# PM_Drive_UI.net
KiCad netlist of a schematic drawn in Altium Designer
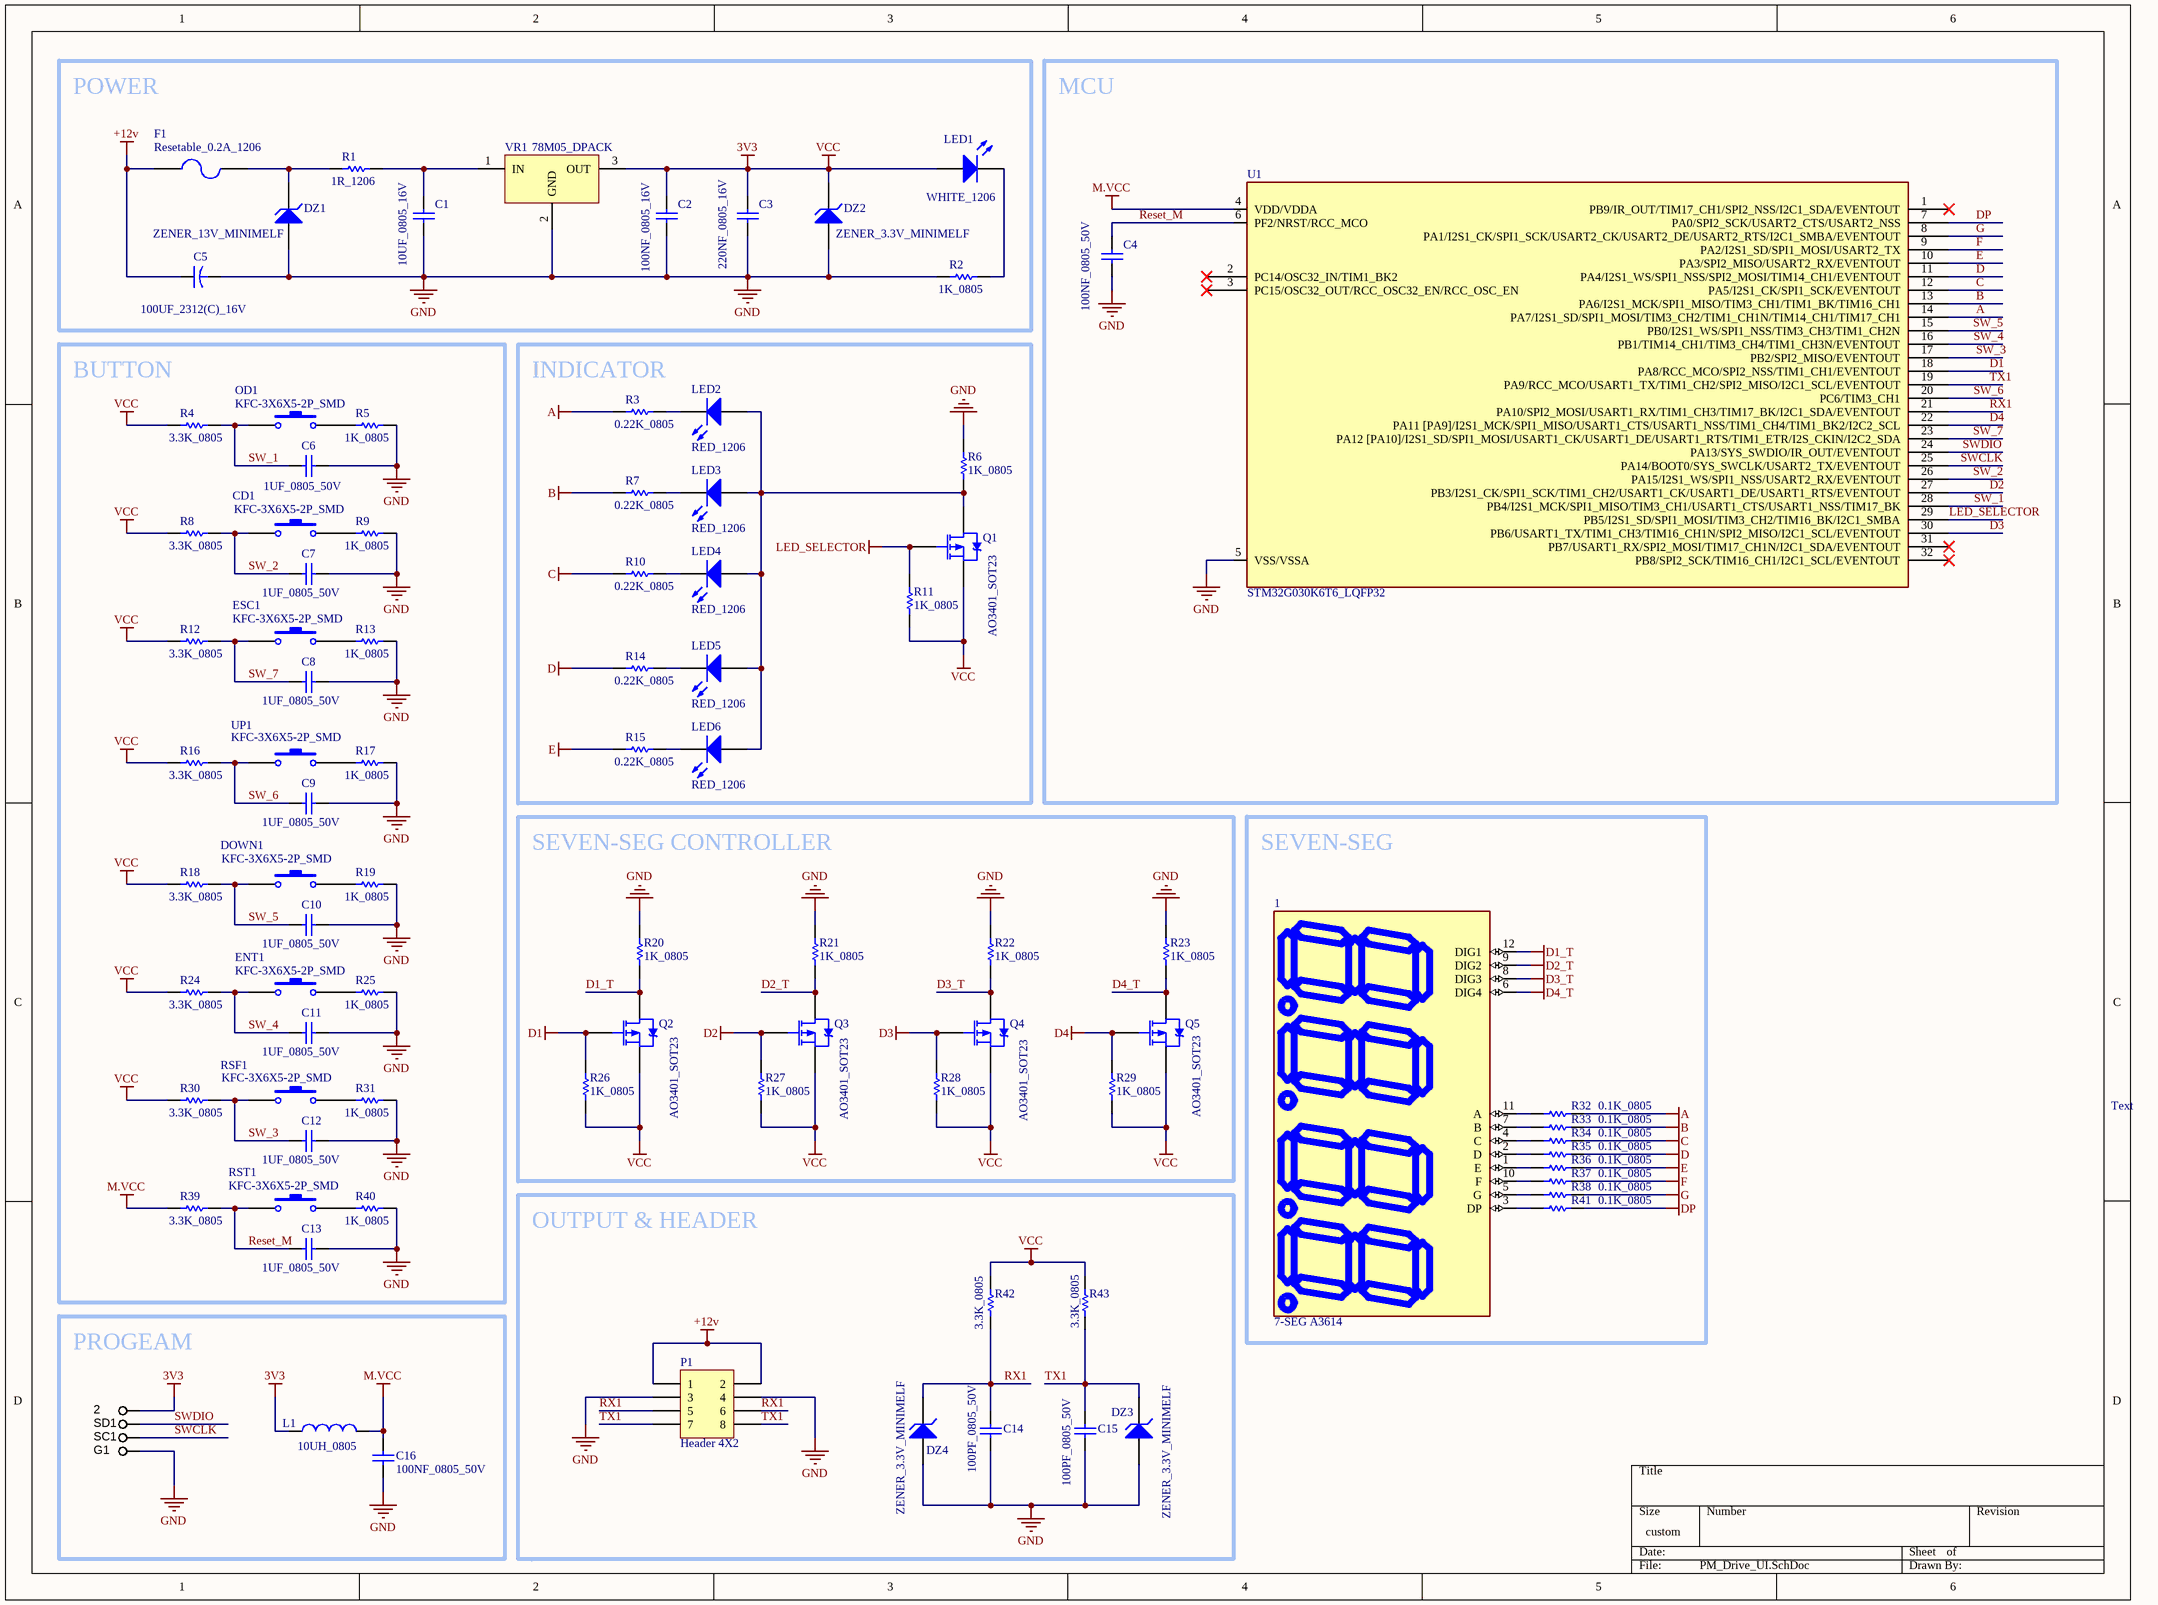
[diagram p0: PM_Drive_UI.SchDoc]

(export (version "E")
  (design (tool "Eeschema 10.0.6"))
  (components
    (comp (ref "1")
      (value "7-SEG A3614")
      (footprint "7Seg_4Digit")
      (libsource (lib "Amirreza") (part "7SEG-4DIGT-12mm"))
    )
    (comp (ref "2")
      (value "~")
      (footprint "TPSMD_D1")
      (description "TEST POINT")
      (fields (field (name "MANF") "MANF") (field (name "MANF_P#") "MANF_P#"))
      (libsource (lib "GTC Schematic") (part "TESTPOINT_SMD"))
    )
    (comp (ref "C1")
      (value "10UF_0805_16V")
      (footprint "Cap_0805_Nominal")
      (libsource (lib "Saeed_New_Lib") (part "Cap"))
    )
    (comp (ref "C2")
      (value "100NF_0805_16V")
      (footprint "Cap_0805_Nominal")
      (libsource (lib "Saeed_New_Lib") (part "Cap"))
    )
    (comp (ref "C3")
      (value "220NF_0805_16V")
      (footprint "Cap_0805_Nominal")
      (libsource (lib "Saeed_New_Lib") (part "Cap"))
    )
    (comp (ref "C4")
      (value "100NF_0805_50V")
      (footprint "Cap_0805_Nominal")
      (libsource (lib "Saeed_New_Lib") (part "Cap"))
    )
    (comp (ref "C5")
      (value "100UF_2312(C)_16V")
      (footprint "Cap_Tantal(6032)_C")
      (libsource (lib "GTC Shem") (part "Cap_Electrical"))
    )
    (comp (ref "C6")
      (value "1UF_0805_50V")
      (footprint "Cap_0805_Nominal")
      (libsource (lib "Saeed_New_Lib") (part "Cap"))
    )
    (comp (ref "C7")
      (value "1UF_0805_50V")
      (footprint "Cap_0805_Nominal")
      (libsource (lib "Saeed_New_Lib") (part "Cap"))
    )
    (comp (ref "C8")
      (value "1UF_0805_50V")
      (footprint "Cap_0805_Nominal")
      (libsource (lib "Saeed_New_Lib") (part "Cap"))
    )
    (comp (ref "C9")
      (value "1UF_0805_50V")
      (footprint "Cap_0805_Nominal")
      (libsource (lib "Saeed_New_Lib") (part "Cap"))
    )
    (comp (ref "C10")
      (value "1UF_0805_50V")
      (footprint "Cap_0805_Nominal")
      (libsource (lib "Saeed_New_Lib") (part "Cap"))
    )
    (comp (ref "C11")
      (value "1UF_0805_50V")
      (footprint "Cap_0805_Nominal")
      (libsource (lib "Saeed_New_Lib") (part "Cap"))
    )
    (comp (ref "C12")
      (value "1UF_0805_50V")
      (footprint "Cap_0805_Nominal")
      (libsource (lib "Saeed_New_Lib") (part "Cap"))
    )
    (comp (ref "C13")
      (value "1UF_0805_50V")
      (footprint "Cap_0805_Nominal")
      (libsource (lib "Saeed_New_Lib") (part "Cap"))
    )
    (comp (ref "C14")
      (value "100PF_0805_50V")
      (footprint "Cap_0805_Nominal")
      (libsource (lib "Saeed_New_Lib") (part "Cap"))
    )
    (comp (ref "C15")
      (value "100PF_0805_50V")
      (footprint "Cap_0805_Nominal")
      (libsource (lib "Saeed_New_Lib") (part "Cap"))
    )
    (comp (ref "C16")
      (value "100NF_0805_50V")
      (footprint "Cap_0805_Nominal")
      (libsource (lib "Saeed_New_Lib") (part "Cap"))
    )
    (comp (ref "CD1")
      (value "KFC-3X6X5-2P_SMD")
      (footprint "SWPBS_SPST_6X3X5")
      (description "Switch")
      (fields (field (name "PUBLISHER") "Altium Limited"))
      (libsource (lib "Miscellaneous Devices") (part "SW-PB"))
    )
    (comp (ref "DOWN1")
      (value "KFC-3X6X5-2P_SMD")
      (footprint "SWPBS_SPST_6X3X5")
      (description "Switch")
      (fields (field (name "PUBLISHER") "Altium Limited"))
      (libsource (lib "Miscellaneous Devices") (part "SW-PB"))
    )
    (comp (ref "DZ1")
      (value "ZENER_13V_MINIMELF")
      (footprint "Diode_ZENER_MINIMELF")
      (libsource (lib "Amirreza") (part "Diode_Zener"))
    )
    (comp (ref "DZ2")
      (value "ZENER_3.3V_MINIMELF")
      (footprint "Diode_ZENER_MINIMELF")
      (libsource (lib "Amirreza") (part "Diode_Zener"))
    )
    (comp (ref "DZ3")
      (value "ZENER_3.3V_MINIMELF")
      (footprint "Diode_ZENER_MINIMELF")
      (libsource (lib "Amirreza") (part "Diode_Zener"))
    )
    (comp (ref "DZ4")
      (value "ZENER_3.3V_MINIMELF")
      (footprint "Diode_ZENER_MINIMELF")
      (libsource (lib "Amirreza") (part "Diode_Zener"))
    )
    (comp (ref "ENT1")
      (value "KFC-3X6X5-2P_SMD")
      (footprint "SWPBS_SPST_6X3X5")
      (description "Switch")
      (fields (field (name "PUBLISHER") "Altium Limited"))
      (libsource (lib "Miscellaneous Devices") (part "SW-PB"))
    )
    (comp (ref "ESC1")
      (value "KFC-3X6X5-2P_SMD")
      (footprint "SWPBS_SPST_6X3X5")
      (description "Switch")
      (fields (field (name "PUBLISHER") "Altium Limited"))
      (libsource (lib "Miscellaneous Devices") (part "SW-PB"))
    )
    (comp (ref "F1")
      (value "Resetable_0.2A_1206")
      (footprint "FUSE_1206")
      (libsource (lib "Amirreza") (part "FUSE"))
    )
    (comp (ref "G1")
      (value "~")
      (footprint "TPSMD_D1")
      (description "TEST POINT")
      (fields (field (name "MANF") "MANF") (field (name "MANF_P#") "MANF_P#"))
      (libsource (lib "GTC Schematic") (part "TESTPOINT_SMD"))
    )
    (comp (ref "L1")
      (value "10UH_0805")
      (footprint "INDUCTOR_0805_Nominal")
      (libsource (lib "Saeed_New_Lib") (part "Inductor"))
    )
    (comp (ref "LED1")
      (value "WHITE_1206")
      (footprint "LED_1206_NOMINAL")
      (libsource (lib "GTC Shem") (part "LED"))
    )
    (comp (ref "LED2")
      (value "RED_1206")
      (footprint "LED_1206_NOMINAL")
      (libsource (lib "GTC Shem") (part "LED"))
    )
    (comp (ref "LED3")
      (value "RED_1206")
      (footprint "LED_1206_NOMINAL")
      (libsource (lib "GTC Shem") (part "LED"))
    )
    (comp (ref "LED4")
      (value "RED_1206")
      (footprint "LED_1206_NOMINAL")
      (libsource (lib "GTC Shem") (part "LED"))
    )
    (comp (ref "LED5")
      (value "RED_1206")
      (footprint "LED_1206_NOMINAL")
      (libsource (lib "GTC Shem") (part "LED"))
    )
    (comp (ref "LED6")
      (value "RED_1206")
      (footprint "LED_1206_NOMINAL")
      (libsource (lib "GTC Shem") (part "LED"))
    )
    (comp (ref "OD1")
      (value "KFC-3X6X5-2P_SMD")
      (footprint "SWPBS_SPST_6X3X5")
      (description "Switch")
      (fields (field (name "PUBLISHER") "Altium Limited"))
      (libsource (lib "Miscellaneous Devices") (part "SW-PB"))
    )
    (comp (ref "P1")
      (value "Header 4X2")
      (footprint "HDR_M_2X4_2.54MM")
      (description "Header, 6-Pin, Dual row")
      (fields (field (name "PUBLISHER") "Altium Limited"))
      (libsource (lib "Amirreza") (part "Header 4X2"))
    )
    (comp (ref "Q1")
      (value "AO3401_SOT23")
      (footprint "SOT23_MOSFET")
      (description "P-Channel MOSFET")
      (fields (field (name "PUBLISHER") "Altium Limited"))
      (libsource (lib "Amirreza") (part "MOSFET-P"))
    )
    (comp (ref "Q2")
      (value "AO3401_SOT23")
      (footprint "SOT23_MOSFET")
      (description "P-Channel MOSFET")
      (fields (field (name "PUBLISHER") "Altium Limited"))
      (libsource (lib "Amirreza") (part "MOSFET-P"))
    )
    (comp (ref "Q3")
      (value "AO3401_SOT23")
      (footprint "SOT23_MOSFET")
      (description "P-Channel MOSFET")
      (fields (field (name "PUBLISHER") "Altium Limited"))
      (libsource (lib "Amirreza") (part "MOSFET-P"))
    )
    (comp (ref "Q4")
      (value "AO3401_SOT23")
      (footprint "SOT23_MOSFET")
      (description "P-Channel MOSFET")
      (fields (field (name "PUBLISHER") "Altium Limited"))
      (libsource (lib "Amirreza") (part "MOSFET-P"))
    )
    (comp (ref "Q5")
      (value "AO3401_SOT23")
      (footprint "SOT23_MOSFET")
      (description "P-Channel MOSFET")
      (fields (field (name "PUBLISHER") "Altium Limited"))
      (libsource (lib "Amirreza") (part "MOSFET-P"))
    )
    (comp (ref "R1")
      (value "1R_1206")
      (footprint "Res_1206_BIG SIZE")
      (libsource (lib "Amir_Library") (part "RES"))
    )
    (comp (ref "R2")
      (value "1K_0805")
      (footprint "Res_0805_Nominal")
      (libsource (lib "Amir_Library") (part "RES"))
    )
    (comp (ref "R3")
      (value "0.22K_0805")
      (footprint "Res_0805_Nominal")
      (libsource (lib "Amir_Library") (part "RES"))
    )
    (comp (ref "R4")
      (value "3.3K_0805")
      (footprint "Res_0805_Nominal")
      (libsource (lib "Amir_Library") (part "RES"))
    )
    (comp (ref "R5")
      (value "1K_0805")
      (footprint "Res_0805_Nominal")
      (libsource (lib "Amir_Library") (part "RES"))
    )
    (comp (ref "R6")
      (value "1K_0805")
      (footprint "Res_0805_Nominal")
      (libsource (lib "Amir_Library") (part "RES"))
    )
    (comp (ref "R7")
      (value "0.22K_0805")
      (footprint "Res_0805_Nominal")
      (libsource (lib "Amir_Library") (part "RES"))
    )
    (comp (ref "R8")
      (value "3.3K_0805")
      (footprint "Res_0805_Nominal")
      (libsource (lib "Amir_Library") (part "RES"))
    )
    (comp (ref "R9")
      (value "1K_0805")
      (footprint "Res_0805_Nominal")
      (libsource (lib "Amir_Library") (part "RES"))
    )
    (comp (ref "R10")
      (value "0.22K_0805")
      (footprint "Res_0805_Nominal")
      (libsource (lib "Amir_Library") (part "RES"))
    )
    (comp (ref "R11")
      (value "1K_0805")
      (footprint "Res_0805_Nominal")
      (libsource (lib "Amir_Library") (part "RES"))
    )
    (comp (ref "R12")
      (value "3.3K_0805")
      (footprint "Res_0805_Nominal")
      (libsource (lib "Amir_Library") (part "RES"))
    )
    (comp (ref "R13")
      (value "1K_0805")
      (footprint "Res_0805_Nominal")
      (libsource (lib "Amir_Library") (part "RES"))
    )
    (comp (ref "R14")
      (value "0.22K_0805")
      (footprint "Res_0805_Nominal")
      (libsource (lib "Amir_Library") (part "RES"))
    )
    (comp (ref "R15")
      (value "0.22K_0805")
      (footprint "Res_0805_Nominal")
      (libsource (lib "Amir_Library") (part "RES"))
    )
    (comp (ref "R16")
      (value "3.3K_0805")
      (footprint "Res_0805_Nominal")
      (libsource (lib "Amir_Library") (part "RES"))
    )
    (comp (ref "R17")
      (value "1K_0805")
      (footprint "Res_0805_Nominal")
      (libsource (lib "Amir_Library") (part "RES"))
    )
    (comp (ref "R18")
      (value "3.3K_0805")
      (footprint "Res_0805_Nominal")
      (libsource (lib "Amir_Library") (part "RES"))
    )
    (comp (ref "R19")
      (value "1K_0805")
      (footprint "Res_0805_Nominal")
      (libsource (lib "Amir_Library") (part "RES"))
    )
    (comp (ref "R20")
      (value "1K_0805")
      (footprint "Res_0805_Nominal")
      (libsource (lib "Amir_Library") (part "RES"))
    )
    (comp (ref "R21")
      (value "1K_0805")
      (footprint "Res_0805_Nominal")
      (libsource (lib "Amir_Library") (part "RES"))
    )
    (comp (ref "R22")
      (value "1K_0805")
      (footprint "Res_0805_Nominal")
      (libsource (lib "Amir_Library") (part "RES"))
    )
    (comp (ref "R23")
      (value "1K_0805")
      (footprint "Res_0805_Nominal")
      (libsource (lib "Amir_Library") (part "RES"))
    )
    (comp (ref "R24")
      (value "3.3K_0805")
      (footprint "Res_0805_Nominal")
      (libsource (lib "Amir_Library") (part "RES"))
    )
    (comp (ref "R25")
      (value "1K_0805")
      (footprint "Res_0805_Nominal")
      (libsource (lib "Amir_Library") (part "RES"))
    )
    (comp (ref "R26")
      (value "1K_0805")
      (footprint "Res_0805_Nominal")
      (libsource (lib "Amir_Library") (part "RES"))
    )
    (comp (ref "R27")
      (value "1K_0805")
      (footprint "Res_0805_Nominal")
      (libsource (lib "Amir_Library") (part "RES"))
    )
    (comp (ref "R28")
      (value "1K_0805")
      (footprint "Res_0805_Nominal")
      (libsource (lib "Amir_Library") (part "RES"))
    )
    (comp (ref "R29")
      (value "1K_0805")
      (footprint "Res_0805_Nominal")
      (libsource (lib "Amir_Library") (part "RES"))
    )
    (comp (ref "R30")
      (value "3.3K_0805")
      (footprint "Res_0805_Nominal")
      (libsource (lib "Amir_Library") (part "RES"))
    )
    (comp (ref "R31")
      (value "1K_0805")
      (footprint "Res_0805_Nominal")
      (libsource (lib "Amir_Library") (part "RES"))
    )
    (comp (ref "R32")
      (value "0.1K_0805")
      (footprint "Res_0805_Nominal")
      (libsource (lib "Amir_Library") (part "RES"))
    )
    (comp (ref "R33")
      (value "0.1K_0805")
      (footprint "Res_0805_Nominal")
      (libsource (lib "Amir_Library") (part "RES"))
    )
    (comp (ref "R34")
      (value "0.1K_0805")
      (footprint "Res_0805_Nominal")
      (libsource (lib "Amir_Library") (part "RES"))
    )
    (comp (ref "R35")
      (value "0.1K_0805")
      (footprint "Res_0805_Nominal")
      (libsource (lib "Amir_Library") (part "RES"))
    )
    (comp (ref "R36")
      (value "0.1K_0805")
      (footprint "Res_0805_Nominal")
      (libsource (lib "Amir_Library") (part "RES"))
    )
    (comp (ref "R37")
      (value "0.1K_0805")
      (footprint "Res_0805_Nominal")
      (libsource (lib "Amir_Library") (part "RES"))
    )
    (comp (ref "R38")
      (value "0.1K_0805")
      (footprint "Res_0805_Nominal")
      (libsource (lib "Amir_Library") (part "RES"))
    )
    (comp (ref "R39")
      (value "3.3K_0805")
      (footprint "Res_0805_Nominal")
      (libsource (lib "Amir_Library") (part "RES"))
    )
    (comp (ref "R40")
      (value "1K_0805")
      (footprint "Res_0805_Nominal")
      (libsource (lib "Amir_Library") (part "RES"))
    )
    (comp (ref "R41")
      (value "0.1K_0805")
      (footprint "Res_0805_Nominal")
      (libsource (lib "Amir_Library") (part "RES"))
    )
    (comp (ref "R42")
      (value "3.3K_0805")
      (footprint "Res_0805_Nominal")
      (libsource (lib "Amir_Library") (part "RES"))
    )
    (comp (ref "R43")
      (value "3.3K_0805")
      (footprint "Res_0805_Nominal")
      (libsource (lib "Amir_Library") (part "RES"))
    )
    (comp (ref "RSF1")
      (value "KFC-3X6X5-2P_SMD")
      (footprint "SWPBS_SPST_6X3X5")
      (description "Switch")
      (fields (field (name "PUBLISHER") "Altium Limited"))
      (libsource (lib "Miscellaneous Devices") (part "SW-PB"))
    )
    (comp (ref "RST1")
      (value "KFC-3X6X5-2P_SMD")
      (footprint "SWPBS_SPST_6X3X5")
      (description "Switch")
      (fields (field (name "PUBLISHER") "Altium Limited"))
      (libsource (lib "Miscellaneous Devices") (part "SW-PB"))
    )
    (comp (ref "SC1")
      (value "~")
      (footprint "TPSMD_D1")
      (description "TEST POINT")
      (fields (field (name "MANF") "MANF") (field (name "MANF_P#") "MANF_P#"))
      (libsource (lib "GTC Schematic") (part "TESTPOINT_SMD"))
    )
    (comp (ref "SD1")
      (value "~")
      (footprint "TPSMD_D1")
      (description "TEST POINT")
      (fields (field (name "MANF") "MANF") (field (name "MANF_P#") "MANF_P#"))
      (libsource (lib "GTC Schematic") (part "TESTPOINT_SMD"))
    )
    (comp (ref "U1")
      (value "STM32G030K6T6_LQFP32")
      (footprint "QFG80_32")
      (fields (field (name "MANF") "ST") (field (name "MANF_P#") "STM32G030K6T6"))
      (libsource (lib "Amirreza") (part "STM32G030K6T6"))
    )
    (comp (ref "UP1")
      (value "KFC-3X6X5-2P_SMD")
      (footprint "SWPBS_SPST_6X3X5")
      (description "Switch")
      (fields (field (name "PUBLISHER") "Altium Limited"))
      (libsource (lib "Miscellaneous Devices") (part "SW-PB"))
    )
    (comp (ref "VR1") (value "78M05_DPACK") (footprint "DPAK") (libsource (lib "Amirreza") (part "78M05")))
  )
  (nets
    (net (code "1") (name "+12v") (class "Default")
      (node (ref "C5") (pin "1") (pinfunction "1_1") (pintype "passive"))
      (node (ref "F1") (pin "1") (pinfunction "1_1") (pintype "passive"))
      (node (ref "P1") (pin "1") (pinfunction "1_1") (pintype "passive"))
      (node (ref "P1") (pin "2") (pinfunction "2_2") (pintype "passive"))
    )
    (net (code "2") (name "/RX1") (class "Default")
      (node (ref "C14") (pin "1") (pinfunction "1_1") (pintype "passive"))
      (node (ref "DZ4") (pin "2") (pinfunction "K_2") (pintype "passive"))
      (node (ref "P1") (pin "5") (pinfunction "5_5") (pintype "passive"))
      (node (ref "P1") (pin "6") (pinfunction "6_6") (pintype "passive"))
      (node (ref "R42") (pin "1") (pinfunction "1_1") (pintype "passive"))
      (node (ref "U1") (pin "21") (pinfunction "PA10/SPI2_MOSI/USART1_RX/TIM1_CH3/TIM17_BK/I2C1_SDA/EVENTOUT_21") (pintype "passive"))
    )
    (net (code "3") (name "/Reset_M") (class "Default")
      (node (ref "C13") (pin "2") (pinfunction "2_2") (pintype "passive"))
      (node (ref "C4") (pin "2") (pinfunction "2_2") (pintype "passive"))
      (node (ref "R39") (pin "2") (pinfunction "2_2") (pintype "passive"))
      (node (ref "RST1") (pin "1") (pinfunction "1_1") (pintype "passive"))
      (node (ref "U1") (pin "6") (pinfunction "PF2/NRST/RCC_MCO_6") (pintype "passive"))
    )
    (net (code "4") (name "/SWCLK") (class "Default")
      (node (ref "SC1") (pin "1") (pinfunction "1_1") (pintype "passive"))
      (node (ref "U1") (pin "25") (pinfunction "PA14/BOOT0/SYS_SWCLK/USART2_TX/EVENTOUT_25") (pintype "passive"))
    )
    (net (code "5") (name "/SWDIO") (class "Default")
      (node (ref "SD1") (pin "1") (pinfunction "1_1") (pintype "passive"))
      (node (ref "U1") (pin "24") (pinfunction "PA13/SYS_SWDIO/IR_OUT/EVENTOUT_24") (pintype "passive"))
    )
    (net (code "6") (name "/SW_1") (class "Default")
      (node (ref "C6") (pin "2") (pinfunction "2_2") (pintype "passive"))
      (node (ref "OD1") (pin "1") (pinfunction "1_1") (pintype "passive"))
      (node (ref "R4") (pin "2") (pinfunction "2_2") (pintype "passive"))
      (node (ref "U1") (pin "28") (pinfunction "PB4/I2S1_MCK/SPI1_MISO/TIM3_CH1/USART1_CTS/USART1_NSS/TIM17_BK_28") (pintype "passive"))
    )
    (net (code "7") (name "/SW_2") (class "Default")
      (node (ref "C7") (pin "2") (pinfunction "2_2") (pintype "passive"))
      (node (ref "CD1") (pin "1") (pinfunction "1_1") (pintype "passive"))
      (node (ref "R8") (pin "2") (pinfunction "2_2") (pintype "passive"))
      (node (ref "U1") (pin "26") (pinfunction "PA15/I2S1_WS/SPI1_NSS/USART2_RX/EVENTOUT_26") (pintype "passive"))
    )
    (net (code "8") (name "/SW_3") (class "Default")
      (node (ref "C12") (pin "2") (pinfunction "2_2") (pintype "passive"))
      (node (ref "R30") (pin "2") (pinfunction "2_2") (pintype "passive"))
      (node (ref "RSF1") (pin "1") (pinfunction "1_1") (pintype "passive"))
      (node (ref "U1") (pin "17") (pinfunction "PB2/SPI2_MISO/EVENTOUT_17") (pintype "passive"))
    )
    (net (code "9") (name "/SW_4") (class "Default")
      (node (ref "C11") (pin "2") (pinfunction "2_2") (pintype "passive"))
      (node (ref "ENT1") (pin "1") (pinfunction "1_1") (pintype "passive"))
      (node (ref "R24") (pin "2") (pinfunction "2_2") (pintype "passive"))
      (node (ref "U1") (pin "16") (pinfunction "PB1/TIM14_CH1/TIM3_CH4/TIM1_CH3N/EVENTOUT_16") (pintype "passive"))
    )
    (net (code "10") (name "/SW_5") (class "Default")
      (node (ref "C10") (pin "2") (pinfunction "2_2") (pintype "passive"))
      (node (ref "DOWN1") (pin "1") (pinfunction "1_1") (pintype "passive"))
      (node (ref "R18") (pin "2") (pinfunction "2_2") (pintype "passive"))
      (node (ref "U1") (pin "15") (pinfunction "PB0/I2S1_WS/SPI1_NSS/TIM3_CH3/TIM1_CH2N_15") (pintype "passive"))
    )
    (net (code "11") (name "/SW_6") (class "Default")
      (node (ref "C9") (pin "2") (pinfunction "2_2") (pintype "passive"))
      (node (ref "R16") (pin "2") (pinfunction "2_2") (pintype "passive"))
      (node (ref "U1") (pin "20") (pinfunction "PC6/TIM3_CH1_20") (pintype "passive"))
      (node (ref "UP1") (pin "1") (pinfunction "1_1") (pintype "passive"))
    )
    (net (code "12") (name "/SW_7") (class "Default")
      (node (ref "C8") (pin "2") (pinfunction "2_2") (pintype "passive"))
      (node (ref "ESC1") (pin "1") (pinfunction "1_1") (pintype "passive"))
      (node (ref "R12") (pin "2") (pinfunction "2_2") (pintype "passive"))
      (node (ref "U1") (pin "23") (pinfunction "PA12_[PA10]/I2S1_SD/SPI1_MOSI/USART1_CK/USART1_DE/USART1_RTS/TIM1_ETR/I2S_CKIN/I2C2_SDA_23") (pintype "passive"))
    )
    (net (code "13") (name "/TX1") (class "Default")
      (node (ref "C15") (pin "1") (pinfunction "1_1") (pintype "passive"))
      (node (ref "DZ3") (pin "2") (pinfunction "K_2") (pintype "passive"))
      (node (ref "P1") (pin "7") (pinfunction "7_7") (pintype "passive"))
      (node (ref "P1") (pin "8") (pinfunction "8_8") (pintype "passive"))
      (node (ref "R43") (pin "1") (pinfunction "1_1") (pintype "passive"))
      (node (ref "U1") (pin "19") (pinfunction "PA9/RCC_MCO/USART1_TX/TIM1_CH2/SPI2_MISO/I2C1_SCL/EVENTOUT_19") (pintype "passive"))
    )
    (net (code "14") (name "3V3") (class "Default")
      (node (ref "2") (pin "1") (pinfunction "1_1") (pintype "passive"))
      (node (ref "C2") (pin "2") (pinfunction "2_2") (pintype "passive"))
      (node (ref "C3") (pin "2") (pinfunction "2_2") (pintype "passive"))
      (node (ref "DZ2") (pin "2") (pinfunction "K_2") (pintype "passive"))
      (node (ref "L1") (pin "1") (pinfunction "1_1") (pintype "passive"))
      (node (ref "LED1") (pin "1") (pinfunction "A_1") (pintype "passive"))
      (node (ref "Q1") (pin "2") (pinfunction "S_2") (pintype "passive"))
      (node (ref "Q2") (pin "2") (pinfunction "S_2") (pintype "passive"))
      (node (ref "Q3") (pin "2") (pinfunction "S_2") (pintype "passive"))
      (node (ref "Q4") (pin "2") (pinfunction "S_2") (pintype "passive"))
      (node (ref "Q5") (pin "2") (pinfunction "S_2") (pintype "passive"))
      (node (ref "R11") (pin "1") (pinfunction "1_1") (pintype "passive"))
      (node (ref "R12") (pin "1") (pinfunction "1_1") (pintype "passive"))
      (node (ref "R16") (pin "1") (pinfunction "1_1") (pintype "passive"))
      (node (ref "R18") (pin "1") (pinfunction "1_1") (pintype "passive"))
      (node (ref "R24") (pin "1") (pinfunction "1_1") (pintype "passive"))
      (node (ref "R26") (pin "1") (pinfunction "1_1") (pintype "passive"))
      (node (ref "R27") (pin "1") (pinfunction "1_1") (pintype "passive"))
      (node (ref "R28") (pin "1") (pinfunction "1_1") (pintype "passive"))
      (node (ref "R29") (pin "1") (pinfunction "1_1") (pintype "passive"))
      (node (ref "R30") (pin "1") (pinfunction "1_1") (pintype "passive"))
      (node (ref "R4") (pin "1") (pinfunction "1_1") (pintype "passive"))
      (node (ref "R42") (pin "2") (pinfunction "2_2") (pintype "passive"))
      (node (ref "R43") (pin "2") (pinfunction "2_2") (pintype "passive"))
      (node (ref "R8") (pin "1") (pinfunction "1_1") (pintype "passive"))
      (node (ref "VR1") (pin "3") (pinfunction "OUT_3") (pintype "passive"))
    )
    (net (code "15") (name "A") (class "Default")
      (node (ref "R3") (pin "1") (pinfunction "1_1") (pintype "passive"))
      (node (ref "R32") (pin "2") (pinfunction "2_2") (pintype "passive"))
      (node (ref "U1") (pin "14") (pinfunction "PA7/I2S1_SD/SPI1_MOSI/TIM3_CH2/TIM1_CH1N/TIM14_CH1/TIM17_CH1_14") (pintype "passive"))
    )
    (net (code "16") (name "B") (class "Default")
      (node (ref "R33") (pin "2") (pinfunction "2_2") (pintype "passive"))
      (node (ref "R7") (pin "1") (pinfunction "1_1") (pintype "passive"))
      (node (ref "U1") (pin "13") (pinfunction "PA6/I2S1_MCK/SPI1_MISO/TIM3_CH1/TIM1_BK/TIM16_CH1_13") (pintype "passive"))
    )
    (net (code "17") (name "C") (class "Default")
      (node (ref "R10") (pin "1") (pinfunction "1_1") (pintype "passive"))
      (node (ref "R34") (pin "1") (pinfunction "1_1") (pintype "passive"))
      (node (ref "U1") (pin "12") (pinfunction "PA5/I2S1_CK/SPI1_SCK/EVENTOUT_12") (pintype "passive"))
    )
    (net (code "18") (name "D") (class "Default")
      (node (ref "R14") (pin "1") (pinfunction "1_1") (pintype "passive"))
      (node (ref "R35") (pin "1") (pinfunction "1_1") (pintype "passive"))
      (node (ref "U1") (pin "11") (pinfunction "PA4/I2S1_WS/SPI1_NSS/SPI2_MOSI/TIM14_CH1/EVENTOUT_11") (pintype "passive"))
    )
    (net (code "19") (name "D1") (class "Default")
      (node (ref "Q2") (pin "1") (pinfunction "G_1") (pintype "passive"))
      (node (ref "R26") (pin "2") (pinfunction "2_2") (pintype "passive"))
      (node (ref "U1") (pin "18") (pinfunction "PA8/RCC_MCO/SPI2_NSS/TIM1_CH1/EVENTOUT_18") (pintype "passive"))
    )
    (net (code "20") (name "D1_T") (class "Default")
      (node (ref "1") (pin "12") (pinfunction "DIG1_12") (pintype "bidirectional"))
      (node (ref "Q2") (pin "3") (pinfunction "D_3") (pintype "passive"))
      (node (ref "R20") (pin "1") (pinfunction "1_1") (pintype "passive"))
    )
    (net (code "21") (name "D2") (class "Default")
      (node (ref "Q3") (pin "1") (pinfunction "G_1") (pintype "passive"))
      (node (ref "R27") (pin "2") (pinfunction "2_2") (pintype "passive"))
      (node (ref "U1") (pin "27") (pinfunction "PB3/I2S1_CK/SPI1_SCK/TIM1_CH2/USART1_CK/USART1_DE/USART1_RTS/EVENTOUT_27") (pintype "passive"))
    )
    (net (code "22") (name "D2_T") (class "Default")
      (node (ref "1") (pin "9") (pinfunction "DIG2_9") (pintype "bidirectional"))
      (node (ref "Q3") (pin "3") (pinfunction "D_3") (pintype "passive"))
      (node (ref "R21") (pin "1") (pinfunction "1_1") (pintype "passive"))
    )
    (net (code "23") (name "D3") (class "Default")
      (node (ref "Q4") (pin "1") (pinfunction "G_1") (pintype "passive"))
      (node (ref "R28") (pin "2") (pinfunction "2_2") (pintype "passive"))
      (node (ref "U1") (pin "30") (pinfunction "PB6/USART1_TX/TIM1_CH3/TIM16_CH1N/SPI2_MISO/I2C1_SCL/EVENTOUT_30") (pintype "passive"))
    )
    (net (code "24") (name "D3_T") (class "Default")
      (node (ref "1") (pin "8") (pinfunction "DIG3_8") (pintype "bidirectional"))
      (node (ref "Q4") (pin "3") (pinfunction "D_3") (pintype "passive"))
      (node (ref "R22") (pin "1") (pinfunction "1_1") (pintype "passive"))
    )
    (net (code "25") (name "D4") (class "Default")
      (node (ref "Q5") (pin "1") (pinfunction "G_1") (pintype "passive"))
      (node (ref "R29") (pin "2") (pinfunction "2_2") (pintype "passive"))
      (node (ref "U1") (pin "22") (pinfunction "PA11_[PA9]/I2S1_MCK/SPI1_MISO/USART1_CTS/USART1_NSS/TIM1_CH4/TIM1_BK2/I2C2_SCL_22") (pintype "passive"))
    )
    (net (code "26") (name "D4_T") (class "Default")
      (node (ref "1") (pin "6") (pinfunction "DIG4_6") (pintype "bidirectional"))
      (node (ref "Q5") (pin "3") (pinfunction "D_3") (pintype "passive"))
      (node (ref "R23") (pin "1") (pinfunction "1_1") (pintype "passive"))
    )
    (net (code "27") (name "DP") (class "Default")
      (node (ref "R41") (pin "1") (pinfunction "1_1") (pintype "passive"))
      (node (ref "U1") (pin "7") (pinfunction "PA0/SPI2_SCK/USART2_CTS/USART2_NSS_7") (pintype "passive"))
    )
    (net (code "28") (name "E") (class "Default")
      (node (ref "R15") (pin "1") (pinfunction "1_1") (pintype "passive"))
      (node (ref "R36") (pin "1") (pinfunction "1_1") (pintype "passive"))
      (node (ref "U1") (pin "10") (pinfunction "PA3/SPI2_MISO/USART2_RX/EVENTOUT_10") (pintype "passive"))
    )
    (net (code "29") (name "F") (class "Default")
      (node (ref "R37") (pin "2") (pinfunction "2_2") (pintype "passive"))
      (node (ref "U1") (pin "9") (pinfunction "PA2/I2S1_SD/SPI1_MOSI/USART2_TX_9") (pintype "passive"))
    )
    (net (code "30") (name "G") (class "Default")
      (node (ref "R38") (pin "1") (pinfunction "1_1") (pintype "passive"))
      (node (ref "U1") (pin "8") (pinfunction "PA1/I2S1_CK/SPI1_SCK/USART2_CK/USART2_DE/USART2_RTS/I2C1_SMBA/EVENTOUT_8") (pintype "passive"))
    )
    (net (code "31") (name "GND") (class "Default")
      (node (ref "C1") (pin "1") (pinfunction "1_1") (pintype "passive"))
      (node (ref "C10") (pin "1") (pinfunction "1_1") (pintype "passive"))
      (node (ref "C11") (pin "1") (pinfunction "1_1") (pintype "passive"))
      (node (ref "C12") (pin "1") (pinfunction "1_1") (pintype "passive"))
      (node (ref "C13") (pin "1") (pinfunction "1_1") (pintype "passive"))
      (node (ref "C14") (pin "2") (pinfunction "2_2") (pintype "passive"))
      (node (ref "C15") (pin "2") (pinfunction "2_2") (pintype "passive"))
      (node (ref "C16") (pin "2") (pinfunction "2_2") (pintype "passive"))
      (node (ref "C2") (pin "1") (pinfunction "1_1") (pintype "passive"))
      (node (ref "C3") (pin "1") (pinfunction "1_1") (pintype "passive"))
      (node (ref "C4") (pin "1") (pinfunction "1_1") (pintype "passive"))
      (node (ref "C5") (pin "2") (pinfunction "2_2") (pintype "passive"))
      (node (ref "C6") (pin "1") (pinfunction "1_1") (pintype "passive"))
      (node (ref "C7") (pin "1") (pinfunction "1_1") (pintype "passive"))
      (node (ref "C8") (pin "1") (pinfunction "1_1") (pintype "passive"))
      (node (ref "C9") (pin "1") (pinfunction "1_1") (pintype "passive"))
      (node (ref "DZ1") (pin "1") (pinfunction "A_1") (pintype "passive"))
      (node (ref "DZ2") (pin "1") (pinfunction "A_1") (pintype "passive"))
      (node (ref "DZ3") (pin "1") (pinfunction "A_1") (pintype "passive"))
      (node (ref "DZ4") (pin "1") (pinfunction "A_1") (pintype "passive"))
      (node (ref "G1") (pin "1") (pinfunction "1_1") (pintype "passive"))
      (node (ref "P1") (pin "3") (pinfunction "3_3") (pintype "passive"))
      (node (ref "P1") (pin "4") (pinfunction "4_4") (pintype "passive"))
      (node (ref "R13") (pin "2") (pinfunction "2_2") (pintype "passive"))
      (node (ref "R17") (pin "2") (pinfunction "2_2") (pintype "passive"))
      (node (ref "R19") (pin "2") (pinfunction "2_2") (pintype "passive"))
      (node (ref "R2") (pin "1") (pinfunction "1_1") (pintype "passive"))
      (node (ref "R20") (pin "2") (pinfunction "2_2") (pintype "passive"))
      (node (ref "R21") (pin "2") (pinfunction "2_2") (pintype "passive"))
      (node (ref "R22") (pin "2") (pinfunction "2_2") (pintype "passive"))
      (node (ref "R23") (pin "2") (pinfunction "2_2") (pintype "passive"))
      (node (ref "R25") (pin "2") (pinfunction "2_2") (pintype "passive"))
      (node (ref "R31") (pin "2") (pinfunction "2_2") (pintype "passive"))
      (node (ref "R40") (pin "2") (pinfunction "2_2") (pintype "passive"))
      (node (ref "R5") (pin "2") (pinfunction "2_2") (pintype "passive"))
      (node (ref "R6") (pin "2") (pinfunction "2_2") (pintype "passive"))
      (node (ref "R9") (pin "2") (pinfunction "2_2") (pintype "passive"))
      (node (ref "U1") (pin "5") (pinfunction "VSS/VSSA_5") (pintype "passive"))
      (node (ref "VR1") (pin "2") (pinfunction "GND_2") (pintype "passive"))
    )
    (net (code "32") (name "LED_SELECTOR") (class "Default")
      (node (ref "Q1") (pin "1") (pinfunction "G_1") (pintype "passive"))
      (node (ref "R11") (pin "2") (pinfunction "2_2") (pintype "passive"))
      (node (ref "U1") (pin "29") (pinfunction "PB5/I2S1_SD/SPI1_MOSI/TIM3_CH2/TIM16_BK/I2C1_SMBA_29") (pintype "passive"))
    )
    (net (code "33") (name "M.VCC") (class "Default")
      (node (ref "C16") (pin "1") (pinfunction "1_1") (pintype "passive"))
      (node (ref "L1") (pin "2") (pinfunction "2_2") (pintype "passive"))
      (node (ref "R39") (pin "1") (pinfunction "1_1") (pintype "passive"))
      (node (ref "U1") (pin "4") (pinfunction "VDD/VDDA_4") (pintype "passive"))
    )
    (net (code "34") (name "Net-(1-A)") (class "Default")
      (node (ref "1") (pin "11") (pinfunction "A_11") (pintype "bidirectional"))
      (node (ref "R32") (pin "1") (pinfunction "1_1") (pintype "passive"))
    )
    (net (code "35") (name "Net-(1-B)") (class "Default")
      (node (ref "1") (pin "7") (pinfunction "B_7") (pintype "bidirectional"))
      (node (ref "R33") (pin "1") (pinfunction "1_1") (pintype "passive"))
    )
    (net (code "36") (name "Net-(1-C)") (class "Default")
      (node (ref "1") (pin "4") (pinfunction "C_4") (pintype "bidirectional"))
      (node (ref "R34") (pin "2") (pinfunction "2_2") (pintype "passive"))
    )
    (net (code "37") (name "Net-(1-D)") (class "Default")
      (node (ref "1") (pin "2") (pinfunction "D_2") (pintype "bidirectional"))
      (node (ref "R35") (pin "2") (pinfunction "2_2") (pintype "passive"))
    )
    (net (code "38") (name "Net-(1-DP)") (class "Default")
      (node (ref "1") (pin "3") (pinfunction "DP_3") (pintype "bidirectional"))
      (node (ref "R41") (pin "2") (pinfunction "2_2") (pintype "passive"))
    )
    (net (code "39") (name "Net-(1-E)") (class "Default")
      (node (ref "1") (pin "1") (pinfunction "E_1") (pintype "bidirectional"))
      (node (ref "R36") (pin "2") (pinfunction "2_2") (pintype "passive"))
    )
    (net (code "40") (name "Net-(1-F)") (class "Default")
      (node (ref "1") (pin "10") (pinfunction "F_10") (pintype "bidirectional"))
      (node (ref "R37") (pin "1") (pinfunction "1_1") (pintype "passive"))
    )
    (net (code "41") (name "Net-(1-G)") (class "Default")
      (node (ref "1") (pin "5") (pinfunction "G_5") (pintype "bidirectional"))
      (node (ref "R38") (pin "2") (pinfunction "2_2") (pintype "passive"))
    )
    (net (code "42") (name "Net-(CD1-Pad2)") (class "Default")
      (node (ref "CD1") (pin "2") (pinfunction "2_2") (pintype "passive"))
      (node (ref "R9") (pin "1") (pinfunction "1_1") (pintype "passive"))
    )
    (net (code "43") (name "Net-(DOWN1-Pad2)") (class "Default")
      (node (ref "DOWN1") (pin "2") (pinfunction "2_2") (pintype "passive"))
      (node (ref "R19") (pin "1") (pinfunction "1_1") (pintype "passive"))
    )
    (net (code "44") (name "Net-(DZ1-K)") (class "Default")
      (node (ref "DZ1") (pin "2") (pinfunction "K_2") (pintype "passive"))
      (node (ref "F1") (pin "2") (pinfunction "2_2") (pintype "passive"))
      (node (ref "R1") (pin "1") (pinfunction "1_1") (pintype "passive"))
    )
    (net (code "45") (name "Net-(ENT1-Pad2)") (class "Default")
      (node (ref "ENT1") (pin "2") (pinfunction "2_2") (pintype "passive"))
      (node (ref "R25") (pin "1") (pinfunction "1_1") (pintype "passive"))
    )
    (net (code "46") (name "Net-(ESC1-Pad2)") (class "Default")
      (node (ref "ESC1") (pin "2") (pinfunction "2_2") (pintype "passive"))
      (node (ref "R13") (pin "1") (pinfunction "1_1") (pintype "passive"))
    )
    (net (code "47") (name "Net-(LED1-K)") (class "Default")
      (node (ref "LED1") (pin "2") (pinfunction "K_2") (pintype "passive"))
      (node (ref "R2") (pin "2") (pinfunction "2_2") (pintype "passive"))
    )
    (net (code "48") (name "Net-(LED2-A)") (class "Default")
      (node (ref "LED2") (pin "1") (pinfunction "A_1") (pintype "passive"))
      (node (ref "LED3") (pin "1") (pinfunction "A_1") (pintype "passive"))
      (node (ref "LED4") (pin "1") (pinfunction "A_1") (pintype "passive"))
      (node (ref "LED5") (pin "1") (pinfunction "A_1") (pintype "passive"))
      (node (ref "LED6") (pin "1") (pinfunction "A_1") (pintype "passive"))
      (node (ref "Q1") (pin "3") (pinfunction "D_3") (pintype "passive"))
      (node (ref "R6") (pin "1") (pinfunction "1_1") (pintype "passive"))
    )
    (net (code "49") (name "Net-(LED2-K)") (class "Default")
      (node (ref "LED2") (pin "2") (pinfunction "K_2") (pintype "passive"))
      (node (ref "R3") (pin "2") (pinfunction "2_2") (pintype "passive"))
    )
    (net (code "50") (name "Net-(LED3-K)") (class "Default")
      (node (ref "LED3") (pin "2") (pinfunction "K_2") (pintype "passive"))
      (node (ref "R7") (pin "2") (pinfunction "2_2") (pintype "passive"))
    )
    (net (code "51") (name "Net-(LED4-K)") (class "Default")
      (node (ref "LED4") (pin "2") (pinfunction "K_2") (pintype "passive"))
      (node (ref "R10") (pin "2") (pinfunction "2_2") (pintype "passive"))
    )
    (net (code "52") (name "Net-(LED5-K)") (class "Default")
      (node (ref "LED5") (pin "2") (pinfunction "K_2") (pintype "passive"))
      (node (ref "R14") (pin "2") (pinfunction "2_2") (pintype "passive"))
    )
    (net (code "53") (name "Net-(LED6-K)") (class "Default")
      (node (ref "LED6") (pin "2") (pinfunction "K_2") (pintype "passive"))
      (node (ref "R15") (pin "2") (pinfunction "2_2") (pintype "passive"))
    )
    (net (code "54") (name "Net-(OD1-Pad2)") (class "Default")
      (node (ref "OD1") (pin "2") (pinfunction "2_2") (pintype "passive"))
      (node (ref "R5") (pin "1") (pinfunction "1_1") (pintype "passive"))
    )
    (net (code "55") (name "Net-(R17-Pad1)") (class "Default")
      (node (ref "R17") (pin "1") (pinfunction "1_1") (pintype "passive"))
      (node (ref "UP1") (pin "2") (pinfunction "2_2") (pintype "passive"))
    )
    (net (code "56") (name "Net-(R31-Pad1)") (class "Default")
      (node (ref "R31") (pin "1") (pinfunction "1_1") (pintype "passive"))
      (node (ref "RSF1") (pin "2") (pinfunction "2_2") (pintype "passive"))
    )
    (net (code "57") (name "Net-(R40-Pad1)") (class "Default")
      (node (ref "R40") (pin "1") (pinfunction "1_1") (pintype "passive"))
      (node (ref "RST1") (pin "2") (pinfunction "2_2") (pintype "passive"))
    )
    (net (code "58") (name "Net-(VR1-IN)") (class "Default")
      (node (ref "C1") (pin "2") (pinfunction "2_2") (pintype "passive"))
      (node (ref "R1") (pin "2") (pinfunction "2_2") (pintype "passive"))
      (node (ref "VR1") (pin "1") (pinfunction "IN_1") (pintype "passive"))
    )
    (net (code "59") (name "unconnected-(U1-PB7{slash}USART1_RX{slash}SPI2_MOSI{slash}TIM17_CH1N{slash}I2C1_SDA{slash}EVENTOUT-Pad31)") (class "Default")
      (node (ref "U1") (pin "31") (pinfunction "PB7/USART1_RX/SPI2_MOSI/TIM17_CH1N/I2C1_SDA/EVENTOUT_31") (pintype "passive+no_connect"))
    )
    (net (code "60") (name "unconnected-(U1-PB8{slash}SPI2_SCK{slash}TIM16_CH1{slash}I2C1_SCL{slash}EVENTOUT-Pad32)") (class "Default")
      (node (ref "U1") (pin "32") (pinfunction "PB8/SPI2_SCK/TIM16_CH1/I2C1_SCL/EVENTOUT_32") (pintype "passive+no_connect"))
    )
    (net (code "61") (name "unconnected-(U1-PB9{slash}IR_OUT{slash}TIM17_CH1{slash}SPI2_NSS{slash}I2C1_SDA{slash}EVENTOUT-Pad1)") (class "Default")
      (node (ref "U1") (pin "1") (pinfunction "PB9/IR_OUT/TIM17_CH1/SPI2_NSS/I2C1_SDA/EVENTOUT_1") (pintype "passive+no_connect"))
    )
    (net (code "62") (name "unconnected-(U1-PC14{slash}OSC32_IN{slash}TIM1_BK2-Pad2)") (class "Default")
      (node (ref "U1") (pin "2") (pinfunction "PC14/OSC32_IN/TIM1_BK2_2") (pintype "passive+no_connect"))
    )
    (net (code "63") (name "unconnected-(U1-PC15{slash}OSC32_OUT{slash}RCC_OSC32_EN{slash}RCC_OSC_EN-Pad3)") (class "Default")
      (node (ref "U1") (pin "3") (pinfunction "PC15/OSC32_OUT/RCC_OSC32_EN/RCC_OSC_EN_3") (pintype "passive+no_connect"))
    )
  )
)
